# dcdc300v.net
KiCad netlist of a schematic drawn in Altium Designer
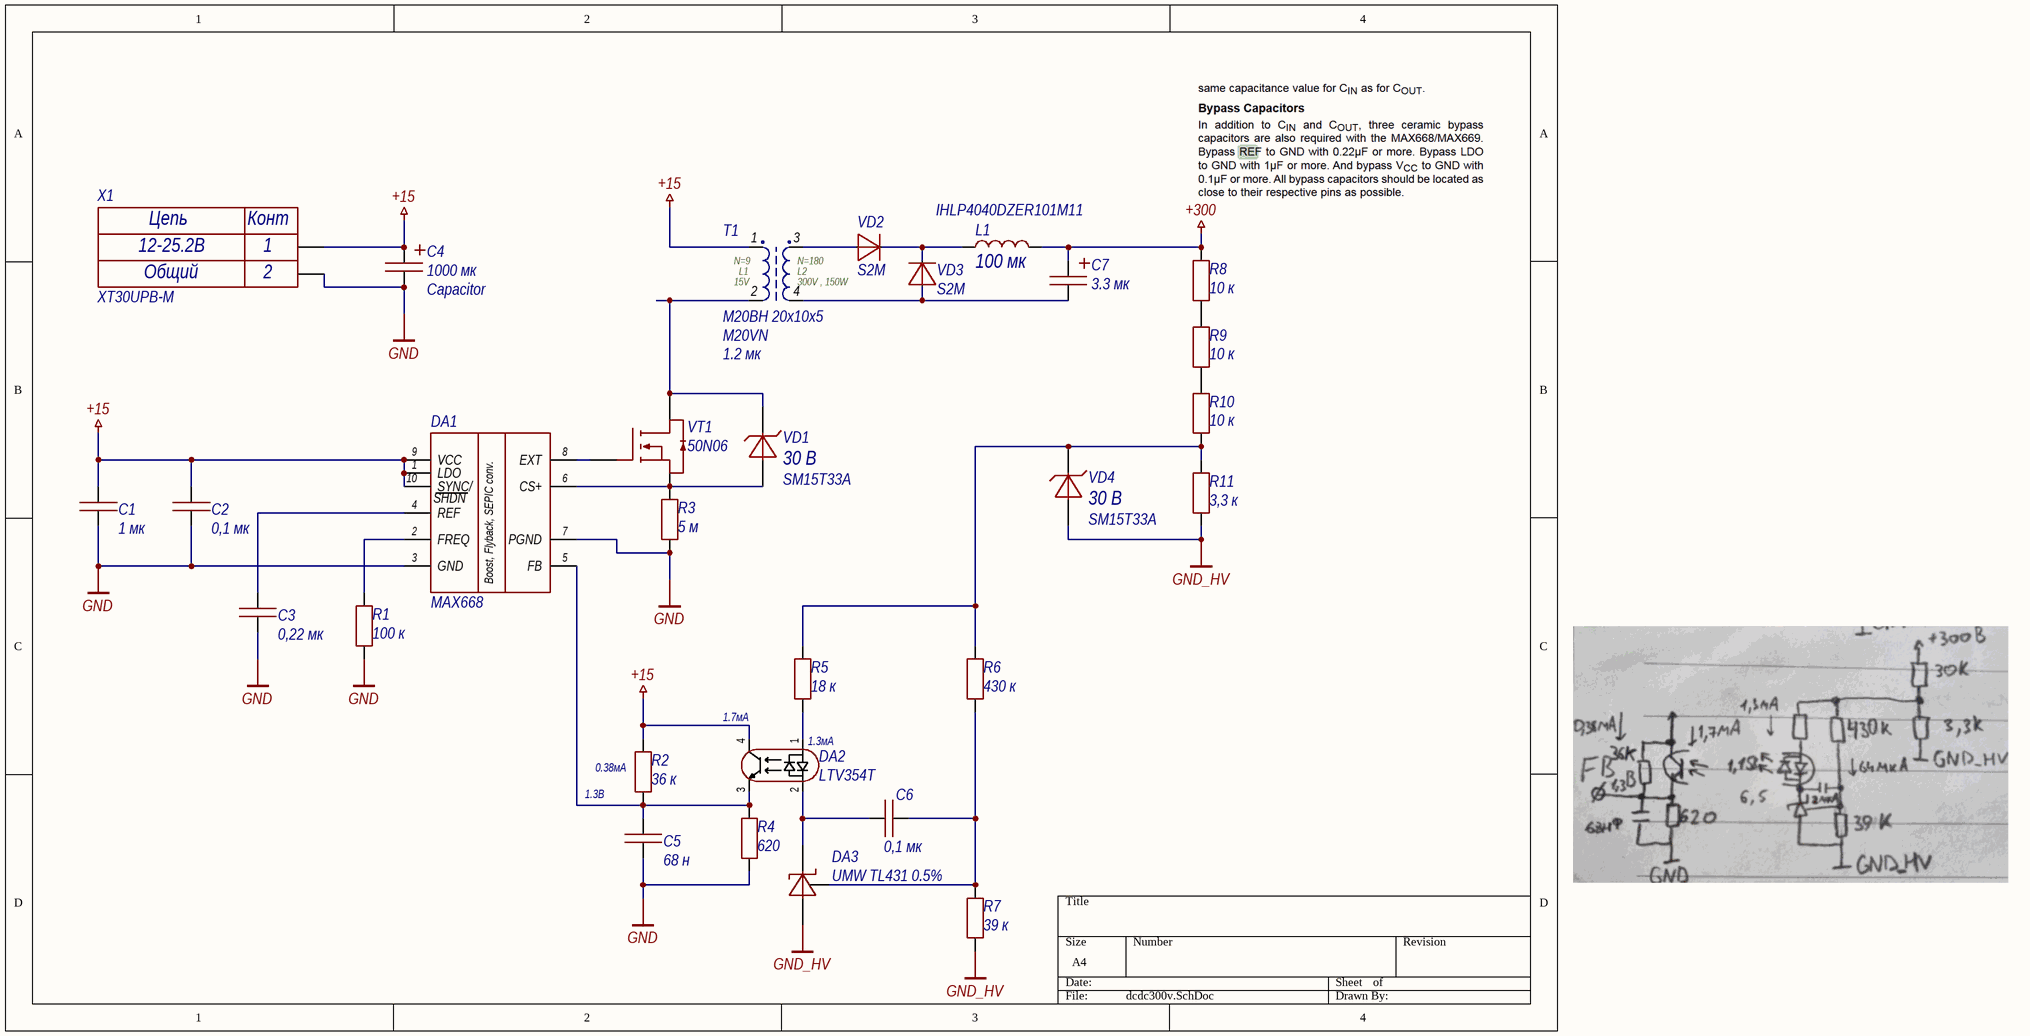
[diagram p0: dcdc300v.SchDoc]

(export (version "E")
  (design (tool "Eeschema 10.0.6"))
  (components
    (comp (ref "C1")
      (value "1 мк")
      (footprint "0603C")
      (description "Конденсатор")
      (fields (field (name "PART NUMBER") "Capacitor_1u_10_50V_X7R_0603C") (field (name "TOLERANCE") "0,1"))
      (libsource (lib "Hydrolib") (part "Capacitor"))
    )
    (comp (ref "C2")
      (value "0,1 мк")
      (footprint "0603C")
      (description "Конденсатор")
      (fields (field (name "PART NUMBER") "Capacitor_0,1u_10_50V_X7R_0603C") (field (name "TOLERANCE") "0,1"))
      (libsource (lib "Hydrolib") (part "Capacitor"))
    )
    (comp (ref "C3")
      (value "0,22 мк")
      (footprint "0603C")
      (description "Конденсатор")
      (fields
        (field (name "PART NUMBER") "Capacitor_0,22u_10_50V_X7R_0603C")
        (field (name "TOLERANCE") "0,1")
      )
      (libsource (lib "Hydrolib") (part "Capacitor"))
    )
    (comp (ref "C4")
      (value "Capacitor")
      (footprint "CAP_EEVFK1V102M")
      (description "Конденсатор алюминиевый электролитический 1000мкФ 25В 20% Low ESR 1100мА SMD12.5x13.5мм")
      (fields
        (field (name "ALTIUM_VALUE") "1000 мк")
        (field (name "PART NUMBER") "EEVFK1V102M")
        (field (name "TOLERANCE") "20")
      )
      (libsource (lib "Hydrolib") (part "Capacitor_polar"))
    )
    (comp (ref "C5")
      (value "68 н")
      (footprint "0603C")
      (description "Конденсатор")
      (fields (field (name "PART NUMBER") "Capacitor_68n_10_50V_X7R_0603C") (field (name "TOLERANCE") "0,1"))
      (libsource (lib "Hydrolib") (part "Capacitor"))
    )
    (comp (ref "C6")
      (value "0,1 мк")
      (footprint "0603C")
      (description "Конденсатор")
      (fields (field (name "PART NUMBER") "Capacitor_0,1u_10_50V_X7R_0603C") (field (name "TOLERANCE") "0,1"))
      (libsource (lib "Hydrolib") (part "Capacitor"))
    )
    (comp (ref "C7")
      (value "3.3 мк")
      (footprint "8x12_radial")
      (description "К50-35, 3.3мкФ, 400В, 105°C, 20%, 8x12мм P:3.5мм")
      (fields (field (name "PART NUMBER") "JRB2G3R3M03500800120000B") (field (name "TOLERANCE") "20"))
      (libsource (lib "Hydrolib") (part "Capacitor_polar"))
    )
    (comp (ref "DA1")
      (value "MAX668")
      (footprint "uSOP10")
      (description "Boost, Flyback, SEPIC преобразователь. 10-uMAX/uSOP")
      (fields (field (name "MP") "MAX668EUB+T") (field (name "MF") "Maxim Integrated"))
      (libsource (lib "Hydrolib") (part "MAX668"))
    )
    (comp (ref "DA2")
      (value "LTV354T")
      (footprint "SOP4-2_54")
      (description "Оптопара с транзисторным выходом, UMW")
      (libsource (lib "Hydrolib") (part "LTV354"))
    )
    (comp (ref "DA3")
      (value "UMW TL431 0.5%")
      (footprint "SOT23-3")
      (description "Источник опорного напряжения , программируемый стабилитрон [SOT-23-3]")
      (libsource (lib "Hydrolib") (part "precision_shunt_regulator"))
    )
    (comp (ref "L1")
      (value "IHLP4040DZER101M11")
      (footprint "IHLP-4040")
      (description "ЧИП-индуктивность экранированная 47мкГн ±20% 3,3A 145мОм 4040")
      (fields (field (name "ALTIUM_VALUE") "100 мк"))
      (libsource (lib "Hydrolib") (part "Inductance"))
    )
    (comp (ref "R1")
      (value "100 к")
      (footprint "0603R")
      (description "Резистор номиналом 100 кОм и точностью 1%")
      (fields (field (name "PART NUMBER") "Resistor_100k_1_0603") (field (name "TOLERANCE") "1%"))
      (libsource (lib "Hydrolib") (part "Resistor"))
    )
    (comp (ref "R2")
      (value "36 к")
      (footprint "0603R")
      (description "Резистор номиналом 36 кОм и точностью 1%")
      (fields (field (name "PART NUMBER") "Resistor_36k_1_0603") (field (name "TOLERANCE") "1%"))
      (libsource (lib "Hydrolib") (part "Resistor"))
    )
    (comp (ref "R3")
      (value "5 м")
      (footprint "2512R")
      (description "Резистор номиналом 5 мОм, точностью 1%, 3Вт")
      (fields (field (name "PART NUMBER") "CRE2512-FZ-R005E-3") (field (name "TOLERANCE") "1%"))
      (libsource (lib "Hydrolib") (part "Resistor"))
    )
    (comp (ref "R4")
      (value "620")
      (footprint "0603R")
      (description "Резистор номиналом 620 Ом и точностью 1%")
      (fields (field (name "PART NUMBER") "Resistor_620_1_0603") (field (name "TOLERANCE") "1%"))
      (libsource (lib "Hydrolib") (part "Resistor"))
    )
    (comp (ref "R5")
      (value "18 к")
      (footprint "0603R")
      (description "Резистор номиналом 18 кОм и точностью 1%")
      (fields (field (name "PART NUMBER") "Resistor_18k_1_0603") (field (name "TOLERANCE") "1%"))
      (libsource (lib "Hydrolib") (part "Resistor"))
    )
    (comp (ref "R6")
      (value "430 к")
      (footprint "0603R")
      (description "Резистор номиналом 430 кОм и точностью 1%")
      (fields (field (name "PART NUMBER") "Resistor_430k_1_0603") (field (name "TOLERANCE") "1%"))
      (libsource (lib "") (part "Resistor_1"))
    )
    (comp (ref "R7")
      (value "39 к")
      (footprint "0603R")
      (description "Резистор номиналом 39 кОм и точностью 1%")
      (fields (field (name "PART NUMBER") "Resistor_39k_1_0603") (field (name "TOLERANCE") "1%"))
      (libsource (lib "Hydrolib") (part "Resistor"))
    )
    (comp (ref "R8")
      (value "10 к")
      (footprint "0603R")
      (description "Резистор номиналом 10 кОм и точностью 1%")
      (fields (field (name "PART NUMBER") "Resistor_10k_1_0603") (field (name "TOLERANCE") "1%"))
      (libsource (lib "Hydrolib") (part "Resistor"))
    )
    (comp (ref "R9")
      (value "10 к")
      (footprint "0603R")
      (description "Резистор номиналом 10 кОм и точностью 1%")
      (fields (field (name "PART NUMBER") "Resistor_10k_1_0603") (field (name "TOLERANCE") "1%"))
      (libsource (lib "Hydrolib") (part "Resistor"))
    )
    (comp (ref "R10")
      (value "10 к")
      (footprint "0603R")
      (description "Резистор номиналом 10 кОм и точностью 1%")
      (fields (field (name "PART NUMBER") "Resistor_10k_1_0603") (field (name "TOLERANCE") "1%"))
      (libsource (lib "Hydrolib") (part "Resistor"))
    )
    (comp (ref "R11")
      (value "3,3 к")
      (footprint "0603R")
      (description "Резистор номиналом 3,3 кОм и точностью 1%")
      (fields (field (name "PART NUMBER") "Resistor_3.3k_1_0603") (field (name "TOLERANCE") "1%"))
      (libsource (lib "Hydrolib") (part "Resistor"))
    )
    (comp (ref "T1")
      (value "M20VN")
      (footprint "M20VN")
      (fields (field (name "ALTIUM_VALUE") "1.2 мк"))
      (libsource (lib "Hydrolib") (part "M20VN"))
    )
    (comp (ref "VD1")
      (value "SM15T33A")
      (footprint "SMC")
      (description "Защитный диод на 30 В, рассеиваемая мощность 1500 Вт")
      (fields (field (name "ALTIUM_VALUE") "30 В"))
      (libsource (lib "Hydrolib") (part "TVS_1_1dir"))
    )
    (comp (ref "VD2")
      (value "S2M")
      (footprint "SMB")
      (description "Выпрямительный диод на 1000 В, ном. ток 2 А")
      (libsource (lib "Hydrolib") (part "Rectifier_diode"))
    )
    (comp (ref "VD3")
      (value "S2M")
      (footprint "SMB")
      (description "Выпрямительный диод на 1000 В, ном. ток 2 А")
      (libsource (lib "Hydrolib") (part "Rectifier_diode"))
    )
    (comp (ref "VD4")
      (value "SM15T33A")
      (footprint "SMC")
      (description "Защитный диод на 30 В, рассеиваемая мощность 1500 Вт")
      (fields (field (name "ALTIUM_VALUE") "30 В"))
      (libsource (lib "Hydrolib") (part "TVS_1_1dir"))
    )
    (comp (ref "VT1")
      (value "50N06")
      (footprint "DPAK")
      (description "N-канальный MOSFET")
      (libsource (lib "Hydrolib") (part "MOSFET N-channel 1"))
    )
    (comp (ref "X1")
      (value "XT30UPB-M")
      (footprint "XT30UPB-M")
      (description "2-пиновый разъем с ключом")
      (fields (field (name "VALUE2") "Общий") (field (name "VALUE1") "12-25.2В"))
      (libsource (lib "Hydrolib") (part "Polar_Conn"))
    )
  )
  (nets
    (net (code "1") (name "+15") (class "Default")
      (node (ref "C1") (pin "2") (pinfunction "2_2") (pintype "passive"))
      (node (ref "C2") (pin "2") (pinfunction "2_2") (pintype "passive"))
      (node (ref "C4") (pin "1") (pinfunction "1_1") (pintype "passive"))
      (node (ref "DA1") (pin "1") (pinfunction "LDO_1") (pintype "passive"))
      (node (ref "DA1") (pin "10") (pinfunction "SYNC/_10") (pintype "passive"))
      (node (ref "DA1") (pin "9") (pinfunction "VCC_9") (pintype "passive"))
      (node (ref "DA2") (pin "4") (pinfunction "CT_4") (pintype "passive"))
      (node (ref "R2") (pin "2") (pinfunction "2_2") (pintype "passive"))
      (node (ref "T1") (pin "1") (pinfunction "1_1") (pintype "passive"))
      (node (ref "X1") (pin "P") (pinfunction "P_P") (pintype "passive"))
    )
    (net (code "2") (name "+300") (class "Default")
      (node (ref "C7") (pin "1") (pinfunction "1_1") (pintype "passive"))
      (node (ref "L1") (pin "2") (pinfunction "2_2") (pintype "passive"))
      (node (ref "R8") (pin "2") (pinfunction "2_2") (pintype "passive"))
    )
    (net (code "3") (name "GND") (class "Default")
      (node (ref "C1") (pin "1") (pinfunction "1_1") (pintype "passive"))
      (node (ref "C2") (pin "1") (pinfunction "1_1") (pintype "passive"))
      (node (ref "C3") (pin "1") (pinfunction "1_1") (pintype "passive"))
      (node (ref "C4") (pin "2") (pinfunction "2_2") (pintype "passive"))
      (node (ref "C5") (pin "1") (pinfunction "1_1") (pintype "passive"))
      (node (ref "DA1") (pin "3") (pinfunction "GND_3") (pintype "passive"))
      (node (ref "DA1") (pin "7") (pinfunction "PGND_7") (pintype "passive"))
      (node (ref "R1") (pin "1") (pinfunction "1_1") (pintype "passive"))
      (node (ref "R3") (pin "1") (pinfunction "1_1") (pintype "passive"))
      (node (ref "R4") (pin "1") (pinfunction "1_1") (pintype "passive"))
      (node (ref "X1") (pin "N") (pinfunction "N_N") (pintype "passive"))
    )
    (net (code "4") (name "GND_HV") (class "Default")
      (node (ref "DA3") (pin "3") (pinfunction "3_3") (pintype "passive"))
      (node (ref "R11") (pin "1") (pinfunction "1_1") (pintype "passive"))
      (node (ref "R7") (pin "1") (pinfunction "1_1") (pintype "passive"))
      (node (ref "VD4") (pin "1") (pinfunction "1_1") (pintype "passive"))
    )
    (net (code "5") (name "Net-(C6-Pad2)") (class "Default")
      (node (ref "C6") (pin "2") (pinfunction "2_2") (pintype "passive"))
      (node (ref "DA3") (pin "1") (pinfunction "1_1") (pintype "passive"))
      (node (ref "R6") (pin "2") (pinfunction "2_2") (pintype "passive"))
      (node (ref "R7") (pin "2") (pinfunction "2_2") (pintype "passive"))
    )
    (net (code "6") (name "Net-(C7-Pad2)") (class "Default")
      (node (ref "C7") (pin "2") (pinfunction "2_2") (pintype "passive"))
      (node (ref "T1") (pin "4") (pinfunction "4_4") (pintype "passive"))
      (node (ref "VD3") (pin "1") (pinfunction "1_1") (pintype "passive"))
    )
    (net (code "7") (name "Net-(DA1-CS+)") (class "Default")
      (node (ref "DA1") (pin "6") (pinfunction "CS+_6") (pintype "passive"))
      (node (ref "R3") (pin "2") (pinfunction "2_2") (pintype "passive"))
      (node (ref "VD1") (pin "1") (pinfunction "1_1") (pintype "passive"))
    )
    (net (code "8") (name "Net-(DA1-EXT)") (class "Default")
      (node (ref "DA1") (pin "8") (pinfunction "EXT_8") (pintype "passive"))
      (node (ref "VT1") (pin "1") (pinfunction "1_1") (pintype "passive"))
    )
    (net (code "9") (name "Net-(DA1-FB)") (class "Default")
      (node (ref "C5") (pin "2") (pinfunction "2_2") (pintype "passive"))
      (node (ref "DA1") (pin "5") (pinfunction "FB_5") (pintype "passive"))
      (node (ref "DA2") (pin "3") (pinfunction "ET_3") (pintype "passive"))
      (node (ref "R2") (pin "1") (pinfunction "1_1") (pintype "passive"))
      (node (ref "R4") (pin "2") (pinfunction "2_2") (pintype "passive"))
    )
    (net (code "10") (name "Net-(DA1-FREQ)") (class "Default")
      (node (ref "DA1") (pin "2") (pinfunction "FREQ_2") (pintype "passive"))
      (node (ref "R1") (pin "2") (pinfunction "2_2") (pintype "passive"))
    )
    (net (code "11") (name "Net-(DA1-REF)") (class "Default")
      (node (ref "C3") (pin "2") (pinfunction "2_2") (pintype "passive"))
      (node (ref "DA1") (pin "4") (pinfunction "REF_4") (pintype "passive"))
    )
    (net (code "12") (name "Net-(DA2-A)") (class "Default")
      (node (ref "DA2") (pin "1") (pinfunction "A_1") (pintype "passive"))
      (node (ref "R5") (pin "1") (pinfunction "1_1") (pintype "passive"))
    )
    (net (code "13") (name "Net-(DA2-C)") (class "Default")
      (node (ref "C6") (pin "1") (pinfunction "1_1") (pintype "passive"))
      (node (ref "DA2") (pin "2") (pinfunction "C_2") (pintype "passive"))
      (node (ref "DA3") (pin "2") (pinfunction "2_2") (pintype "passive"))
    )
    (net (code "14") (name "Net-(L1-Pad1)") (class "Default")
      (node (ref "L1") (pin "1") (pinfunction "1_1") (pintype "passive"))
      (node (ref "VD2") (pin "2") (pinfunction "2_2") (pintype "passive"))
      (node (ref "VD3") (pin "2") (pinfunction "2_2") (pintype "passive"))
    )
    (net (code "15") (name "Net-(R8-Pad1)") (class "Default")
      (node (ref "R8") (pin "1") (pinfunction "1_1") (pintype "passive"))
      (node (ref "R9") (pin "2") (pinfunction "2_2") (pintype "passive"))
    )
    (net (code "16") (name "Net-(R10-Pad1)") (class "Default")
      (node (ref "R10") (pin "1") (pinfunction "1_1") (pintype "passive"))
      (node (ref "R11") (pin "2") (pinfunction "2_2") (pintype "passive"))
      (node (ref "R5") (pin "2") (pinfunction "2_2") (pintype "passive"))
      (node (ref "R6") (pin "1") (pinfunction "1_1") (pintype "passive"))
      (node (ref "VD4") (pin "2") (pinfunction "2_2") (pintype "passive"))
    )
    (net (code "17") (name "Net-(R10-Pad2)") (class "Default")
      (node (ref "R10") (pin "2") (pinfunction "2_2") (pintype "passive"))
      (node (ref "R9") (pin "1") (pinfunction "1_1") (pintype "passive"))
    )
    (net (code "18") (name "Net-(T1-Pad2)") (class "Default")
      (node (ref "T1") (pin "2") (pinfunction "2_2") (pintype "passive"))
      (node (ref "VD1") (pin "2") (pinfunction "2_2") (pintype "passive"))
      (node (ref "VT1") (pin "2") (pinfunction "2_2") (pintype "passive"))
    )
    (net (code "19") (name "Net-(T1-Pad3)") (class "Default")
      (node (ref "T1") (pin "3") (pinfunction "3_3") (pintype "passive"))
      (node (ref "VD2") (pin "1") (pinfunction "1_1") (pintype "passive"))
    )
    (net (code "20") (name "unconnected-(VT1-Pad3)") (class "Default")
      (node (ref "VT1") (pin "3") (pinfunction "3_3") (pintype "passive"))
    )
  )
)
